# untitled.net
KiCad netlist of a schematic drawn in EAGLE
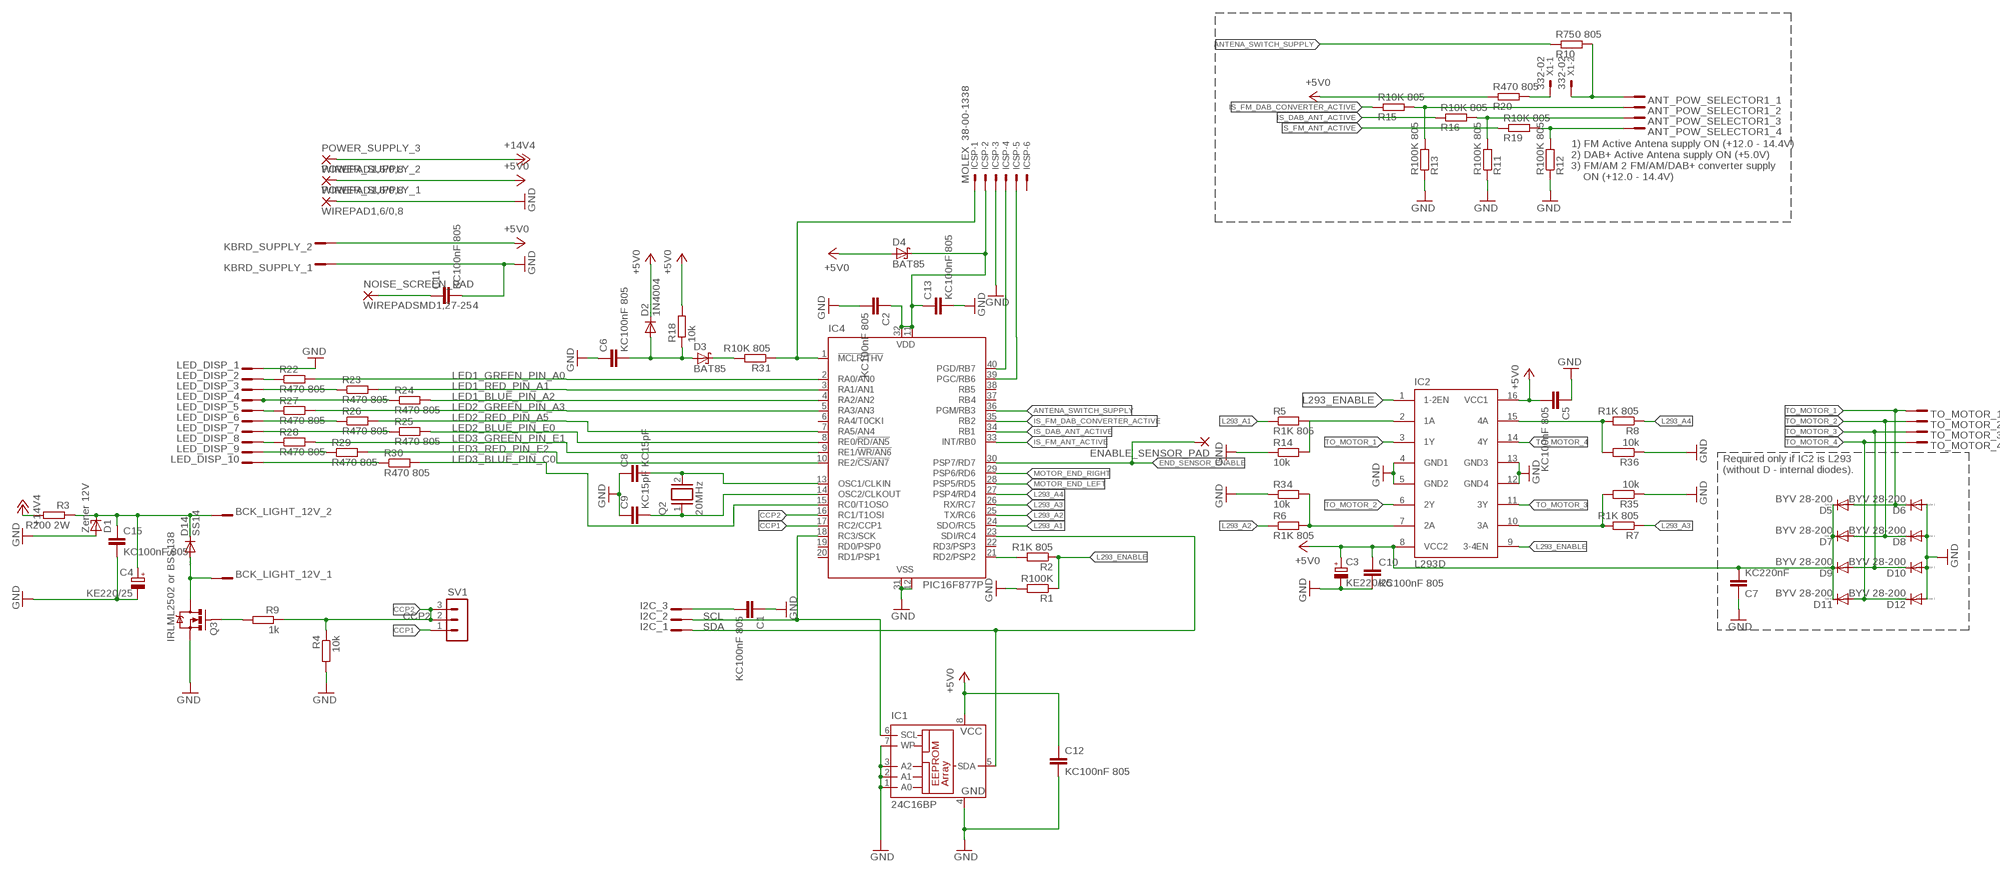
[diagram p0: schematic, sheet 1, part 1 of 2]
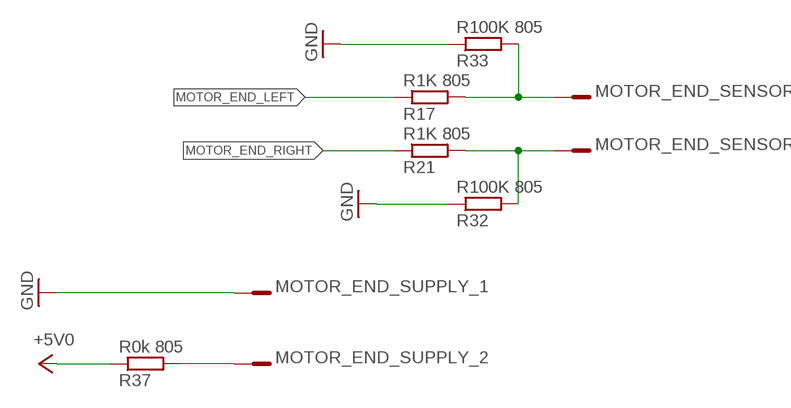
[diagram p1: schematic, sheet 1, part 2 of 2]

(export (version "E")
  (design (tool "Eeschema 10.0.6"))
  (components
    (comp (ref "ANT_POW_SELECTOR1")
      (value "JST_4_PIN_B4B-PH-KS")
      (footprint "eagle-import:B4B-PH-KS")
      (libsource (lib "eagle-import") (part "JST_4_PIN_B4B-PH-KS"))
    )
    (comp (ref "BCK_LIGHT_12V")
      (value "JST_2_PIN_B2B-XH-A")
      (footprint "eagle-import:B2B-XH-A")
      (libsource (lib "eagle-import") (part "JST_2_PIN_B2B-XH-A"))
    )
    (comp (ref "C1")
      (value "KC100nF 805")
      (footprint "eagle-import:C0805")
      (libsource (lib "eagle-import") (part "C-EUC0805"))
    )
    (comp (ref "C2")
      (value "KC100nF 805")
      (footprint "eagle-import:C0805")
      (libsource (lib "eagle-import") (part "C-EUC0805"))
    )
    (comp (ref "C3")
      (value "KE220/25")
      (footprint "eagle-import:E3,5-8")
      (libsource (lib "eagle-import") (part "CPOL-EUE3.5-8"))
    )
    (comp (ref "C4")
      (value "KE220/25")
      (footprint "eagle-import:TT2D7")
      (libsource (lib "eagle-import") (part "CPOL-EUTT2D7"))
    )
    (comp (ref "C5")
      (value "KC100nF 805")
      (footprint "eagle-import:C0805")
      (libsource (lib "eagle-import") (part "C-EUC0805"))
    )
    (comp (ref "C6")
      (value "KC100nF 805")
      (footprint "eagle-import:C0805")
      (libsource (lib "eagle-import") (part "C-EUC0805"))
    )
    (comp (ref "C7")
      (value "KC220nF")
      (footprint "eagle-import:C050-030X075")
      (libsource (lib "eagle-import") (part "C-EU050-030X075"))
    )
    (comp (ref "C8")
      (value "KC15pF")
      (footprint "eagle-import:C025-030X050")
      (libsource (lib "eagle-import") (part "C-EU025-030X050"))
    )
    (comp (ref "C9")
      (value "KC15pF")
      (footprint "eagle-import:C025-030X050")
      (libsource (lib "eagle-import") (part "C-EU025-030X050"))
    )
    (comp (ref "C10")
      (value "KC100nF 805")
      (footprint "eagle-import:C0805")
      (libsource (lib "eagle-import") (part "C-EUC0805"))
    )
    (comp (ref "C11")
      (value "KC100nF 805")
      (footprint "eagle-import:C0805")
      (libsource (lib "eagle-import") (part "C-EUC0805"))
    )
    (comp (ref "C12")
      (value "KC100nF 805")
      (footprint "eagle-import:C0805")
      (libsource (lib "eagle-import") (part "C-EUC0805"))
    )
    (comp (ref "C13")
      (value "KC100nF 805")
      (footprint "eagle-import:C0805")
      (libsource (lib "eagle-import") (part "C-EUC0805"))
    )
    (comp (ref "C15")
      (value "KC100nF 805")
      (footprint "eagle-import:C0805")
      (libsource (lib "eagle-import") (part "C-EUC0805"))
    )
    (comp (ref "D1")
      (value "Zener 12V")
      (footprint "eagle-import:ZDIO-5")
      (libsource (lib "eagle-import") (part "ZENER-DIODEZD-5"))
    )
    (comp (ref "D2")
      (value "1N4004")
      (footprint "eagle-import:DO41-7.6")
      (libsource (lib "eagle-import") (part "1N4004DO41-7.6"))
    )
    (comp (ref "D3")
      (value "BAT85")
      (footprint "eagle-import:DO34-5")
      (libsource (lib "eagle-import") (part "BAT85DO34-5"))
    )
    (comp (ref "D4")
      (value "BAT85")
      (footprint "eagle-import:DO34-5")
      (libsource (lib "eagle-import") (part "BAT85DO34-5"))
    )
    (comp (ref "D5")
      (value "BYV 28-200")
      (footprint "eagle-import:SOD64-10")
      (libsource (lib "eagle-import") (part "BYV28"))
    )
    (comp (ref "D6")
      (value "BYV 28-200")
      (footprint "eagle-import:SOD64-10")
      (libsource (lib "eagle-import") (part "BYV28"))
    )
    (comp (ref "D7")
      (value "BYV 28-200")
      (footprint "eagle-import:SOD64-10")
      (libsource (lib "eagle-import") (part "BYV28"))
    )
    (comp (ref "D8")
      (value "BYV 28-200")
      (footprint "eagle-import:SOD64-10")
      (libsource (lib "eagle-import") (part "BYV28"))
    )
    (comp (ref "D9")
      (value "BYV 28-200")
      (footprint "eagle-import:SOD64-10")
      (libsource (lib "eagle-import") (part "BYV28"))
    )
    (comp (ref "D10")
      (value "BYV 28-200")
      (footprint "eagle-import:SOD64-10")
      (libsource (lib "eagle-import") (part "BYV28"))
    )
    (comp (ref "D11")
      (value "BYV 28-200")
      (footprint "eagle-import:SOD64-10")
      (libsource (lib "eagle-import") (part "BYV28"))
    )
    (comp (ref "D12")
      (value "BYV 28-200")
      (footprint "eagle-import:SOD64-10")
      (libsource (lib "eagle-import") (part "BYV28"))
    )
    (comp (ref "D14")
      (value "SS14")
      (footprint "eagle-import:SMB")
      (libsource (lib "eagle-import") (part "DIODE-SMB"))
    )
    (comp (ref "ENABLE_SENSOR_PAD")
      (value "SMD2")
      (footprint "eagle-import:SMD1,27-2,54")
      (libsource (lib "eagle-import") (part "SMD2"))
    )
    (comp (ref "I2C")
      (value "JST_3_PIN_B3B-PH-KS")
      (footprint "eagle-import:B3B-PH-KS")
      (libsource (lib "eagle-import") (part "JST_3_PIN_B3B-PH-KS"))
    )
    (comp (ref "IC1")
      (value "24C16BP")
      (footprint "eagle-import:DIL8")
      (fields (field (name "MPN") "AT24C16B-PU"))
      (libsource (lib "eagle-import") (part "24PC16B"))
    )
    (comp (ref "IC2")
      (value "L293D")
      (footprint "eagle-import:DIL16")
      (libsource (lib "eagle-import") (part "L293D"))
    )
    (comp (ref "IC4")
      (value "PIC16F877P")
      (footprint "eagle-import:DIL40")
      (fields (field (name "MF") "MICROCHIP") (field (name "MPN") "PIC16F877-04/P"))
      (libsource (lib "eagle-import") (part "PIC16F87P7"))
    )
    (comp (ref "ICSP")
      (value "MOLEX 38-00-1338")
      (footprint "eagle-import:6410-06")
      (libsource (lib "eagle-import") (part "22-?-0627-2061"))
    )
    (comp (ref "KBRD_SUPPLY")
      (value "JST_2_PIN_B2B-PH-KS")
      (footprint "eagle-import:B2B-PH-KS")
      (libsource (lib "eagle-import") (part "JST_2_PIN_B2B-PH-KS"))
    )
    (comp (ref "LED_DISP")
      (value "JST_10_PIN_B10B-PH-KS")
      (footprint "eagle-import:B10B-PH-KS")
      (libsource (lib "eagle-import") (part "JST_10_PIN_B10B-PH-KS"))
    )
    (comp (ref "MOTOR_END_SENSOR")
      (value "JST_2_PIN_B2B-PH-KS")
      (footprint "eagle-import:B2B-PH-KS")
      (libsource (lib "eagle-import") (part "JST_2_PIN_B2B-PH-KS"))
    )
    (comp (ref "MOTOR_END_SUPPLY")
      (value "JST_2_PIN_B2B-PH-KS")
      (footprint "eagle-import:B2B-PH-KS")
      (libsource (lib "eagle-import") (part "JST_2_PIN_B2B-PH-KS"))
    )
    (comp (ref "NOISE_SCREEN_PAD")
      (value "WIREPADSMD1,27-254")
      (footprint "eagle-import:SMD1,27-2,54")
      (libsource (lib "eagle-import") (part "WIREPADSMD1,27-254"))
    )
    (comp (ref "POWER_SUPPLY_1")
      (value "WIREPAD1,6/0,8")
      (footprint "eagle-import:1,6_0,8")
      (libsource (lib "eagle-import") (part "WIREPAD1,6/0,8"))
    )
    (comp (ref "POWER_SUPPLY_2")
      (value "WIREPAD1,6/0,8")
      (footprint "eagle-import:1,6_0,8")
      (libsource (lib "eagle-import") (part "WIREPAD1,6/0,8"))
    )
    (comp (ref "POWER_SUPPLY_3")
      (value "WIREPAD1,6/0,8")
      (footprint "eagle-import:1,6_0,8")
      (libsource (lib "eagle-import") (part "WIREPAD1,6/0,8"))
    )
    (comp (ref "Q2")
      (value "20MHz")
      (footprint "eagle-import:QS")
      (libsource (lib "eagle-import") (part "XTAL/S"))
    )
    (comp (ref "Q3")
      (value "IRLML2502 or BSS138")
      (footprint "eagle-import:SOT23-3")
      (libsource (lib "eagle-import") (part "MOSFET-NCHANNELSMD"))
    )
    (comp (ref "R1")
      (value "R100K")
      (footprint "eagle-import:0204_7")
      (libsource (lib "eagle-import") (part "resistor_R-EU_0204/7"))
    )
    (comp (ref "R2")
      (value "R1K 805")
      (footprint "eagle-import:R0805")
      (libsource (lib "eagle-import") (part "resistor_R-EU_R0805"))
    )
    (comp (ref "R3")
      (value "R200 2W")
      (footprint "eagle-import:0207_12")
      (libsource (lib "eagle-import") (part "R-EU_0207/12"))
    )
    (comp (ref "R4")
      (value "10k")
      (footprint "eagle-import:M0805")
      (libsource (lib "eagle-import") (part "R-EU_M0805"))
    )
    (comp (ref "R5")
      (value "R1K 805")
      (footprint "eagle-import:R0805")
      (libsource (lib "eagle-import") (part "resistor_R-EU_R0805"))
    )
    (comp (ref "R6")
      (value "R1K 805")
      (footprint "eagle-import:R0805")
      (libsource (lib "eagle-import") (part "resistor_R-EU_R0805"))
    )
    (comp (ref "R7")
      (value "R1K 805")
      (footprint "eagle-import:R0805")
      (libsource (lib "eagle-import") (part "resistor_R-EU_R0805"))
    )
    (comp (ref "R8")
      (value "R1K 805")
      (footprint "eagle-import:R0805")
      (libsource (lib "eagle-import") (part "resistor_R-EU_R0805"))
    )
    (comp (ref "R9")
      (value "1k")
      (footprint "eagle-import:0207_12")
      (libsource (lib "eagle-import") (part "R-EU_0207/12"))
    )
    (comp (ref "R10")
      (value "R750 805")
      (footprint "eagle-import:R0805")
      (libsource (lib "eagle-import") (part "resistor_R-EU_R0805"))
    )
    (comp (ref "R11")
      (value "R100K 805")
      (footprint "eagle-import:R0805")
      (libsource (lib "eagle-import") (part "resistor_R-EU_R0805"))
    )
    (comp (ref "R12")
      (value "R100K 805")
      (footprint "eagle-import:R0805")
      (libsource (lib "eagle-import") (part "resistor_R-EU_R0805"))
    )
    (comp (ref "R13")
      (value "R100K 805")
      (footprint "eagle-import:R0805")
      (libsource (lib "eagle-import") (part "resistor_R-EU_R0805"))
    )
    (comp (ref "R14")
      (value "10k")
      (footprint "eagle-import:0204V")
      (libsource (lib "eagle-import") (part "resistor_R-EU_0204/2V"))
    )
    (comp (ref "R15")
      (value "R10K 805")
      (footprint "eagle-import:R0805")
      (libsource (lib "eagle-import") (part "resistor_R-EU_R0805"))
    )
    (comp (ref "R16")
      (value "R10K 805")
      (footprint "eagle-import:R0805")
      (libsource (lib "eagle-import") (part "resistor_R-EU_R0805"))
    )
    (comp (ref "R17")
      (value "R1K 805")
      (footprint "eagle-import:R0805")
      (libsource (lib "eagle-import") (part "resistor_R-EU_R0805"))
    )
    (comp (ref "R18")
      (value "10k")
      (footprint "eagle-import:R0805")
      (libsource (lib "eagle-import") (part "resistor_R-EU_R0805"))
    )
    (comp (ref "R19")
      (value "R10K 805")
      (footprint "eagle-import:R0805")
      (libsource (lib "eagle-import") (part "resistor_R-EU_R0805"))
    )
    (comp (ref "R20")
      (value "R470 805")
      (footprint "eagle-import:R0805")
      (libsource (lib "eagle-import") (part "resistor_R-EU_R0805"))
    )
    (comp (ref "R21")
      (value "R1K 805")
      (footprint "eagle-import:R0805")
      (libsource (lib "eagle-import") (part "resistor_R-EU_R0805"))
    )
    (comp (ref "R22")
      (value "R470 805")
      (footprint "eagle-import:R0805")
      (libsource (lib "eagle-import") (part "resistor_R-EU_R0805"))
    )
    (comp (ref "R23")
      (value "R470 805")
      (footprint "eagle-import:R0805")
      (libsource (lib "eagle-import") (part "resistor_R-EU_R0805"))
    )
    (comp (ref "R24")
      (value "R470 805")
      (footprint "eagle-import:R0805")
      (libsource (lib "eagle-import") (part "resistor_R-EU_R0805"))
    )
    (comp (ref "R25")
      (value "R470 805")
      (footprint "eagle-import:R0805")
      (libsource (lib "eagle-import") (part "resistor_R-EU_R0805"))
    )
    (comp (ref "R26")
      (value "R470 805")
      (footprint "eagle-import:R0805")
      (libsource (lib "eagle-import") (part "resistor_R-EU_R0805"))
    )
    (comp (ref "R27")
      (value "R470 805")
      (footprint "eagle-import:R0805")
      (libsource (lib "eagle-import") (part "resistor_R-EU_R0805"))
    )
    (comp (ref "R28")
      (value "R470 805")
      (footprint "eagle-import:R0805")
      (libsource (lib "eagle-import") (part "resistor_R-EU_R0805"))
    )
    (comp (ref "R29")
      (value "R470 805")
      (footprint "eagle-import:R0805")
      (libsource (lib "eagle-import") (part "resistor_R-EU_R0805"))
    )
    (comp (ref "R30")
      (value "R470 805")
      (footprint "eagle-import:R0805")
      (libsource (lib "eagle-import") (part "resistor_R-EU_R0805"))
    )
    (comp (ref "R31")
      (value "R10K 805")
      (footprint "eagle-import:R0805")
      (libsource (lib "eagle-import") (part "resistor_R-EU_R0805"))
    )
    (comp (ref "R32")
      (value "R100K 805")
      (footprint "eagle-import:R0805")
      (libsource (lib "eagle-import") (part "resistor_R-EU_R0805"))
    )
    (comp (ref "R33")
      (value "R100K 805")
      (footprint "eagle-import:R0805")
      (libsource (lib "eagle-import") (part "resistor_R-EU_R0805"))
    )
    (comp (ref "R34")
      (value "10k")
      (footprint "eagle-import:0204_5")
      (libsource (lib "eagle-import") (part "resistor_R-EU_0204/5"))
    )
    (comp (ref "R35")
      (value "10k")
      (footprint "eagle-import:0204_7")
      (libsource (lib "eagle-import") (part "resistor_R-EU_0204/7"))
    )
    (comp (ref "R36")
      (value "10k")
      (footprint "eagle-import:0204_7")
      (libsource (lib "eagle-import") (part "resistor_R-EU_0204/7"))
    )
    (comp (ref "R37")
      (value "R0k 805")
      (footprint "eagle-import:R0805")
      (libsource (lib "eagle-import") (part "resistor_R-EU_R0805"))
    )
    (comp (ref "SV1")
      (value "MA03-1")
      (footprint "eagle-import:MA03-1")
      (libsource (lib "eagle-import") (part "MA03-1"))
    )
    (comp (ref "TO_MOTOR")
      (value "JST_4_PIN_B4B-XH-A")
      (footprint "eagle-import:B4B-XH-A")
      (libsource (lib "eagle-import") (part "JST_4_PIN_B4B-XH-A"))
    )
    (comp (ref "X1")
      (value "332-02")
      (footprint "eagle-import:332-02")
      (libsource (lib "eagle-import") (part "332-02"))
    )
  )
  (nets
    (net (code "1") (name "+5V0") (class "Default")
      (node (ref "C10") (pin "1") (pinfunction "1_1") (pintype "passive"))
      (node (ref "C12") (pin "1") (pinfunction "1_1") (pintype "passive"))
      (node (ref "C3") (pin "+") (pinfunction "+_+") (pintype "passive"))
      (node (ref "C5") (pin "2") (pinfunction "2_2") (pintype "passive"))
      (node (ref "C7") (pin "2") (pinfunction "2_2") (pintype "passive"))
      (node (ref "D11") (pin "C") (pinfunction "C_C") (pintype "passive"))
      (node (ref "D2") (pin "C") (pinfunction "C_C") (pintype "passive"))
      (node (ref "D4") (pin "A") (pinfunction "A_A") (pintype "passive"))
      (node (ref "D5") (pin "C") (pinfunction "C_C") (pintype "passive"))
      (node (ref "D7") (pin "C") (pinfunction "C_C") (pintype "passive"))
      (node (ref "D9") (pin "C") (pinfunction "C_C") (pintype "passive"))
      (node (ref "IC1") (pin "8") (pinfunction "VCC_8") (pintype "power_in"))
      (node (ref "IC2") (pin "16") (pinfunction "VCC1_16") (pintype "power_in"))
      (node (ref "IC2") (pin "8") (pinfunction "VCC2_8") (pintype "power_in"))
      (node (ref "KBRD_SUPPLY") (pin "P$2") (pinfunction "P$1_P$2") (pintype "bidirectional"))
      (node (ref "POWER_SUPPLY_2") (pin "1") (pinfunction "P_1") (pintype "passive"))
      (node (ref "R18") (pin "2") (pinfunction "2_2") (pintype "passive"))
      (node (ref "R20") (pin "1") (pinfunction "1_1") (pintype "passive"))
      (node (ref "R37") (pin "1") (pinfunction "1_1") (pintype "passive"))
    )
    (net (code "2") (name "+14V4") (class "Default")
      (node (ref "POWER_SUPPLY_3") (pin "1") (pinfunction "P_1") (pintype "passive"))
      (node (ref "R3") (pin "2") (pinfunction "2_2") (pintype "passive"))
    )
    (net (code "3") (name "/LED1_BLUE_PIN_A2") (class "Default")
      (node (ref "IC4") (pin "4") (pinfunction "RA2/AN2_4") (pintype "bidirectional"))
      (node (ref "R24") (pin "2") (pinfunction "2_2") (pintype "passive"))
    )
    (net (code "4") (name "/LED1_GREEN_PIN_A0") (class "Default")
      (node (ref "IC4") (pin "2") (pinfunction "RA0/AN0_2") (pintype "bidirectional"))
      (node (ref "R22") (pin "2") (pinfunction "2_2") (pintype "passive"))
    )
    (net (code "5") (name "/LED1_RED_PIN_A1") (class "Default")
      (node (ref "IC4") (pin "3") (pinfunction "RA1/AN1_3") (pintype "bidirectional"))
      (node (ref "R23") (pin "2") (pinfunction "2_2") (pintype "passive"))
    )
    (net (code "6") (name "/LED2_BLUE_PIN_E0") (class "Default")
      (node (ref "IC4") (pin "8") (pinfunction "RE0/~{RD/AN5}_8") (pintype "bidirectional"))
      (node (ref "R25") (pin "2") (pinfunction "2_2") (pintype "passive"))
    )
    (net (code "7") (name "/LED2_GREEN_PIN_A3") (class "Default")
      (node (ref "IC4") (pin "5") (pinfunction "RA3/AN3_5") (pintype "bidirectional"))
      (node (ref "R27") (pin "2") (pinfunction "2_2") (pintype "passive"))
    )
    (net (code "8") (name "/LED2_RED_PIN_A5") (class "Default")
      (node (ref "IC4") (pin "7") (pinfunction "RA5/AN4_7") (pintype "bidirectional"))
      (node (ref "R26") (pin "2") (pinfunction "2_2") (pintype "passive"))
    )
    (net (code "9") (name "/LED3_BLUE_PIN_C0") (class "Default")
      (node (ref "IC4") (pin "15") (pinfunction "RC0/T1OSO_15") (pintype "bidirectional"))
      (node (ref "R30") (pin "2") (pinfunction "2_2") (pintype "passive"))
    )
    (net (code "10") (name "/LED3_GREEN_PIN_E1") (class "Default")
      (node (ref "IC4") (pin "9") (pinfunction "RE1/~{WR/AN6}_9") (pintype "bidirectional"))
      (node (ref "R28") (pin "2") (pinfunction "2_2") (pintype "passive"))
    )
    (net (code "11") (name "/LED3_RED_PIN_E2") (class "Default")
      (node (ref "IC4") (pin "10") (pinfunction "RE2/~{CS/AN7}_10") (pintype "bidirectional"))
      (node (ref "R29") (pin "2") (pinfunction "2_2") (pintype "passive"))
    )
    (net (code "12") (name "/SCL") (class "Default")
      (node (ref "I2C") (pin "P$2") (pinfunction "P$1_P$2") (pintype "bidirectional"))
      (node (ref "IC1") (pin "6") (pinfunction "SCL_6") (pintype "input"))
      (node (ref "IC4") (pin "18") (pinfunction "RC3/SCK_18") (pintype "bidirectional"))
    )
    (net (code "13") (name "/SDA") (class "Default")
      (node (ref "I2C") (pin "P$1") (pinfunction "P$1_P$1") (pintype "bidirectional"))
      (node (ref "IC1") (pin "5") (pinfunction "SDA_5") (pintype "bidirectional"))
      (node (ref "IC4") (pin "23") (pinfunction "SDI/RC4_23") (pintype "bidirectional"))
    )
    (net (code "14") (name "ANTENA_SWITCH_SUPPLY") (class "Default")
      (node (ref "IC4") (pin "36") (pinfunction "PGM/RB3_36") (pintype "bidirectional"))
      (node (ref "R10") (pin "1") (pinfunction "1_1") (pintype "passive"))
    )
    (net (code "15") (name "CCP1") (class "Default")
      (node (ref "IC4") (pin "17") (pinfunction "RC2/CCP1_17") (pintype "bidirectional"))
      (node (ref "SV1") (pin "1") (pinfunction "1_1") (pintype "passive"))
    )
    (net (code "16") (name "CCP2") (class "Default")
      (node (ref "IC4") (pin "16") (pinfunction "RC1/T1OSI_16") (pintype "bidirectional"))
      (node (ref "R4") (pin "1") (pinfunction "1_1") (pintype "passive"))
      (node (ref "R9") (pin "1") (pinfunction "1_1") (pintype "passive"))
      (node (ref "SV1") (pin "2") (pinfunction "2_2") (pintype "passive"))
      (node (ref "SV1") (pin "3") (pinfunction "3_3") (pintype "passive"))
    )
    (net (code "17") (name "END_SENSOR_ENABLE") (class "Default")
      (node (ref "ENABLE_SENSOR_PAD") (pin "1") (pinfunction "P_1") (pintype "passive"))
      (node (ref "IC4") (pin "30") (pinfunction "PSP7/RD7_30") (pintype "bidirectional"))
    )
    (net (code "18") (name "GND") (class "Default")
      (node (ref "C1") (pin "1") (pinfunction "1_1") (pintype "passive"))
      (node (ref "C10") (pin "2") (pinfunction "2_2") (pintype "passive"))
      (node (ref "C11") (pin "2") (pinfunction "2_2") (pintype "passive"))
      (node (ref "C12") (pin "2") (pinfunction "2_2") (pintype "passive"))
      (node (ref "C13") (pin "2") (pinfunction "2_2") (pintype "passive"))
      (node (ref "C15") (pin "2") (pinfunction "2_2") (pintype "passive"))
      (node (ref "C2") (pin "2") (pinfunction "2_2") (pintype "passive"))
      (node (ref "C3") (pin "-") (pinfunction "-_-") (pintype "passive"))
      (node (ref "C4") (pin "-") (pinfunction "-_-") (pintype "passive"))
      (node (ref "C5") (pin "1") (pinfunction "1_1") (pintype "passive"))
      (node (ref "C6") (pin "1") (pinfunction "1_1") (pintype "passive"))
      (node (ref "C7") (pin "1") (pinfunction "1_1") (pintype "passive"))
      (node (ref "C8") (pin "1") (pinfunction "1_1") (pintype "passive"))
      (node (ref "C9") (pin "1") (pinfunction "1_1") (pintype "passive"))
      (node (ref "D1") (pin "A") (pinfunction "A_A") (pintype "passive"))
      (node (ref "D10") (pin "A") (pinfunction "A_A") (pintype "passive"))
      (node (ref "D12") (pin "A") (pinfunction "A_A") (pintype "passive"))
      (node (ref "D6") (pin "A") (pinfunction "A_A") (pintype "passive"))
      (node (ref "D8") (pin "A") (pinfunction "A_A") (pintype "passive"))
      (node (ref "IC1") (pin "1") (pinfunction "A0_1") (pintype "input"))
      (node (ref "IC1") (pin "2") (pinfunction "A1_2") (pintype "input"))
      (node (ref "IC1") (pin "3") (pinfunction "A2_3") (pintype "input"))
      (node (ref "IC1") (pin "4") (pinfunction "GND_4") (pintype "power_in"))
      (node (ref "IC1") (pin "7") (pinfunction "WP_7") (pintype "input"))
      (node (ref "IC2") (pin "12") (pinfunction "GND4_12") (pintype "power_in"))
      (node (ref "IC2") (pin "13") (pinfunction "GND3_13") (pintype "power_in"))
      (node (ref "IC2") (pin "4") (pinfunction "GND1_4") (pintype "power_in"))
      (node (ref "IC2") (pin "5") (pinfunction "GND2_5") (pintype "power_in"))
      (node (ref "IC4") (pin "12") (pinfunction "VSS_12") (pintype "power_in"))
      (node (ref "IC4") (pin "31") (pinfunction "VSS_31") (pintype "power_in"))
      (node (ref "ICSP") (pin "3") (pinfunction "S_3") (pintype "passive"))
      (node (ref "KBRD_SUPPLY") (pin "P$1") (pinfunction "P$1_P$1") (pintype "bidirectional"))
      (node (ref "LED_DISP") (pin "P$1") (pinfunction "P$1_P$1") (pintype "bidirectional"))
      (node (ref "MOTOR_END_SUPPLY") (pin "P$1") (pinfunction "P$1_P$1") (pintype "bidirectional"))
      (node (ref "POWER_SUPPLY_1") (pin "1") (pinfunction "P_1") (pintype "passive"))
      (node (ref "Q3") (pin "2") (pinfunction "S_2") (pintype "passive"))
      (node (ref "R1") (pin "2") (pinfunction "2_2") (pintype "passive"))
      (node (ref "R11") (pin "1") (pinfunction "1_1") (pintype "passive"))
      (node (ref "R12") (pin "1") (pinfunction "1_1") (pintype "passive"))
      (node (ref "R13") (pin "1") (pinfunction "1_1") (pintype "passive"))
      (node (ref "R14") (pin "1") (pinfunction "1_1") (pintype "passive"))
      (node (ref "R32") (pin "1") (pinfunction "1_1") (pintype "passive"))
      (node (ref "R33") (pin "1") (pinfunction "1_1") (pintype "passive"))
      (node (ref "R34") (pin "1") (pinfunction "1_1") (pintype "passive"))
      (node (ref "R35") (pin "1") (pinfunction "1_1") (pintype "passive"))
      (node (ref "R36") (pin "1") (pinfunction "1_1") (pintype "passive"))
      (node (ref "R4") (pin "2") (pinfunction "2_2") (pintype "passive"))
    )
    (net (code "19") (name "IS_DAB_ANT_ACTIVE") (class "Default")
      (node (ref "IC4") (pin "34") (pinfunction "RB1_34") (pintype "bidirectional"))
      (node (ref "R16") (pin "1") (pinfunction "1_1") (pintype "passive"))
    )
    (net (code "20") (name "IS_FM_ANT_ACTIVE") (class "Default")
      (node (ref "IC4") (pin "33") (pinfunction "INT/RB0_33") (pintype "bidirectional"))
      (node (ref "R19") (pin "1") (pinfunction "1_1") (pintype "passive"))
    )
    (net (code "21") (name "IS_FM_DAB_CONVERTER_ACTIVE") (class "Default")
      (node (ref "IC4") (pin "35") (pinfunction "RB2_35") (pintype "bidirectional"))
      (node (ref "R15") (pin "1") (pinfunction "1_1") (pintype "passive"))
    )
    (net (code "22") (name "L293_A1") (class "Default")
      (node (ref "IC4") (pin "24") (pinfunction "SDO/RC5_24") (pintype "bidirectional"))
      (node (ref "R5") (pin "1") (pinfunction "1_1") (pintype "passive"))
    )
    (net (code "23") (name "L293_A2") (class "Default")
      (node (ref "IC4") (pin "25") (pinfunction "TX/RC6_25") (pintype "bidirectional"))
      (node (ref "R6") (pin "1") (pinfunction "1_1") (pintype "passive"))
    )
    (net (code "24") (name "L293_A3") (class "Default")
      (node (ref "IC4") (pin "26") (pinfunction "RX/RC7_26") (pintype "bidirectional"))
      (node (ref "R7") (pin "1") (pinfunction "1_1") (pintype "passive"))
    )
    (net (code "25") (name "L293_A4") (class "Default")
      (node (ref "IC4") (pin "27") (pinfunction "PSP4/RD4_27") (pintype "bidirectional"))
      (node (ref "R8") (pin "1") (pinfunction "1_1") (pintype "passive"))
    )
    (net (code "26") (name "L293_ENABLE") (class "Default")
      (node (ref "IC2") (pin "1") (pinfunction "1-2EN_1") (pintype "input"))
      (node (ref "IC2") (pin "9") (pinfunction "3-4EN_9") (pintype "input"))
      (node (ref "R1") (pin "1") (pinfunction "1_1") (pintype "passive"))
      (node (ref "R2") (pin "1") (pinfunction "1_1") (pintype "passive"))
    )
    (net (code "27") (name "MOTOR_END_LEFT") (class "Default")
      (node (ref "IC4") (pin "28") (pinfunction "PSP5/RD5_28") (pintype "bidirectional"))
      (node (ref "R17") (pin "1") (pinfunction "1_1") (pintype "passive"))
    )
    (net (code "28") (name "MOTOR_END_RIGHT") (class "Default")
      (node (ref "IC4") (pin "29") (pinfunction "PSP6/RD6_29") (pintype "bidirectional"))
      (node (ref "R21") (pin "1") (pinfunction "1_1") (pintype "passive"))
    )
    (net (code "29") (name "Net-(ANT_POW_SELECTOR1B-P$1)") (class "Default")
      (node (ref "ANT_POW_SELECTOR1") (pin "P$2") (pinfunction "P$1_P$2") (pintype "bidirectional"))
      (node (ref "R13") (pin "2") (pinfunction "2_2") (pintype "passive"))
      (node (ref "R15") (pin "2") (pinfunction "2_2") (pintype "passive"))
    )
    (net (code "30") (name "Net-(ANT_POW_SELECTOR1C-P$1)") (class "Default")
      (node (ref "ANT_POW_SELECTOR1") (pin "P$3") (pinfunction "P$1_P$3") (pintype "bidirectional"))
      (node (ref "R11") (pin "2") (pinfunction "2_2") (pintype "passive"))
      (node (ref "R16") (pin "2") (pinfunction "2_2") (pintype "passive"))
    )
    (net (code "31") (name "Net-(ANT_POW_SELECTOR1D-P$1)") (class "Default")
      (node (ref "ANT_POW_SELECTOR1") (pin "P$4") (pinfunction "P$1_P$4") (pintype "bidirectional"))
      (node (ref "R12") (pin "2") (pinfunction "2_2") (pintype "passive"))
      (node (ref "R19") (pin "2") (pinfunction "2_2") (pintype "passive"))
    )
    (net (code "32") (name "Net-(BCK_LIGHT_12VB-P$1)") (class "Default")
      (node (ref "BCK_LIGHT_12V") (pin "P$2") (pinfunction "P$1_P$2") (pintype "bidirectional"))
      (node (ref "C15") (pin "1") (pinfunction "1_1") (pintype "passive"))
      (node (ref "C4") (pin "+") (pinfunction "+_+") (pintype "passive"))
      (node (ref "D1") (pin "C") (pinfunction "C_C") (pintype "passive"))
      (node (ref "D14") (pin "C") (pinfunction "C_C") (pintype "passive"))
      (node (ref "R3") (pin "1") (pinfunction "1_1") (pintype "passive"))
    )
    (net (code "33") (name "Net-(C6-Pad2)") (class "Default")
      (node (ref "C6") (pin "2") (pinfunction "2_2") (pintype "passive"))
      (node (ref "D2") (pin "A") (pinfunction "A_A") (pintype "passive"))
      (node (ref "D3") (pin "A") (pinfunction "A_A") (pintype "passive"))
      (node (ref "R18") (pin "1") (pinfunction "1_1") (pintype "passive"))
    )
    (net (code "34") (name "Net-(D3-PadC)") (class "Default")
      (node (ref "D3") (pin "C") (pinfunction "C_C") (pintype "passive"))
      (node (ref "R31") (pin "2") (pinfunction "2_2") (pintype "passive"))
    )
    (net (code "35") (name "Net-(I2CC-P$1)") (class "Default")
      (node (ref "C1") (pin "2") (pinfunction "2_2") (pintype "passive"))
      (node (ref "I2C") (pin "P$3") (pinfunction "P$1_P$3") (pintype "bidirectional"))
    )
    (net (code "36") (name "Net-(IC2-1A)") (class "Default")
      (node (ref "IC2") (pin "2") (pinfunction "1A_2") (pintype "input"))
      (node (ref "R14") (pin "2") (pinfunction "2_2") (pintype "passive"))
      (node (ref "R5") (pin "2") (pinfunction "2_2") (pintype "passive"))
    )
    (net (code "37") (name "Net-(IC2-2A)") (class "Default")
      (node (ref "IC2") (pin "7") (pinfunction "2A_7") (pintype "input"))
      (node (ref "R34") (pin "2") (pinfunction "2_2") (pintype "passive"))
      (node (ref "R6") (pin "2") (pinfunction "2_2") (pintype "passive"))
    )
    (net (code "38") (name "Net-(IC2-3A)") (class "Default")
      (node (ref "IC2") (pin "10") (pinfunction "3A_10") (pintype "input"))
      (node (ref "R35") (pin "2") (pinfunction "2_2") (pintype "passive"))
      (node (ref "R7") (pin "2") (pinfunction "2_2") (pintype "passive"))
    )
    (net (code "39") (name "Net-(IC2-4A)") (class "Default")
      (node (ref "IC2") (pin "15") (pinfunction "4A_15") (pintype "input"))
      (node (ref "R36") (pin "2") (pinfunction "2_2") (pintype "passive"))
      (node (ref "R8") (pin "2") (pinfunction "2_2") (pintype "passive"))
    )
    (net (code "40") (name "Net-(IC4-OSC1{slash}CLKIN)") (class "Default")
      (node (ref "C8") (pin "2") (pinfunction "2_2") (pintype "passive"))
      (node (ref "IC4") (pin "13") (pinfunction "OSC1/CLKIN_13") (pintype "input"))
      (node (ref "Q2") (pin "2") (pinfunction "2_2") (pintype "passive"))
    )
    (net (code "41") (name "Net-(IC4-OSC2{slash}CLKOUT)") (class "Default")
      (node (ref "C9") (pin "2") (pinfunction "2_2") (pintype "passive"))
      (node (ref "IC4") (pin "14") (pinfunction "OSC2/CLKOUT_14") (pintype "output"))
      (node (ref "Q2") (pin "1") (pinfunction "1_1") (pintype "passive"))
    )
    (net (code "42") (name "Net-(IC4-PGC{slash}RB6)") (class "Default")
      (node (ref "IC4") (pin "39") (pinfunction "PGC/RB6_39") (pintype "bidirectional"))
      (node (ref "ICSP") (pin "5") (pinfunction "S_5") (pintype "passive"))
    )
    (net (code "43") (name "Net-(IC4-PGD{slash}RB7)") (class "Default")
      (node (ref "IC4") (pin "40") (pinfunction "PGD/RB7_40") (pintype "bidirectional"))
      (node (ref "ICSP") (pin "4") (pinfunction "S_4") (pintype "passive"))
    )
    (net (code "44") (name "Net-(IC4-RD2{slash}PSP2)") (class "Default")
      (node (ref "IC4") (pin "21") (pinfunction "RD2/PSP2_21") (pintype "bidirectional"))
      (node (ref "R2") (pin "2") (pinfunction "2_2") (pintype "passive"))
    )
    (net (code "45") (name "Net-(IC4-~{MCLR{slash}THV})") (class "Default")
      (node (ref "IC4") (pin "1") (pinfunction "~{MCLR/THV}_1") (pintype "input"))
      (node (ref "ICSP") (pin "1") (pinfunction "S_1") (pintype "passive"))
      (node (ref "R31") (pin "1") (pinfunction "1_1") (pintype "passive"))
    )
    (net (code "46") (name "Net-(ICSPB-S)") (class "Default")
      (node (ref "C13") (pin "1") (pinfunction "1_1") (pintype "passive"))
      (node (ref "C2") (pin "1") (pinfunction "1_1") (pintype "passive"))
      (node (ref "D4") (pin "C") (pinfunction "C_C") (pintype "passive"))
      (node (ref "IC4") (pin "11") (pinfunction "VDD_11") (pintype "power_in"))
      (node (ref "IC4") (pin "32") (pinfunction "VDD_32") (pintype "power_in"))
      (node (ref "ICSP") (pin "2") (pinfunction "S_2") (pintype "passive"))
    )
    (net (code "47") (name "Net-(LED_DISPB-P$1)") (class "Default")
      (node (ref "LED_DISP") (pin "P$10") (pinfunction "P$1_P$10") (pintype "bidirectional"))
      (node (ref "R30") (pin "1") (pinfunction "1_1") (pintype "passive"))
    )
    (net (code "48") (name "Net-(LED_DISPC-P$1)") (class "Default")
      (node (ref "LED_DISP") (pin "P$2") (pinfunction "P$1_P$2") (pintype "bidirectional"))
      (node (ref "R22") (pin "1") (pinfunction "1_1") (pintype "passive"))
    )
    (net (code "49") (name "Net-(LED_DISPD-P$1)") (class "Default")
      (node (ref "LED_DISP") (pin "P$3") (pinfunction "P$1_P$3") (pintype "bidirectional"))
      (node (ref "R23") (pin "1") (pinfunction "1_1") (pintype "passive"))
    )
    (net (code "50") (name "Net-(LED_DISPE-P$1)") (class "Default")
      (node (ref "LED_DISP") (pin "P$4") (pinfunction "P$1_P$4") (pintype "bidirectional"))
      (node (ref "R24") (pin "1") (pinfunction "1_1") (pintype "passive"))
    )
    (net (code "51") (name "Net-(LED_DISPF-P$1)") (class "Default")
      (node (ref "LED_DISP") (pin "P$5") (pinfunction "P$1_P$5") (pintype "bidirectional"))
      (node (ref "R27") (pin "1") (pinfunction "1_1") (pintype "passive"))
    )
    (net (code "52") (name "Net-(LED_DISPG-P$1)") (class "Default")
      (node (ref "LED_DISP") (pin "P$6") (pinfunction "P$1_P$6") (pintype "bidirectional"))
      (node (ref "R26") (pin "1") (pinfunction "1_1") (pintype "passive"))
    )
    (net (code "53") (name "Net-(LED_DISPH-P$1)") (class "Default")
      (node (ref "LED_DISP") (pin "P$7") (pinfunction "P$1_P$7") (pintype "bidirectional"))
      (node (ref "R25") (pin "1") (pinfunction "1_1") (pintype "passive"))
    )
    (net (code "54") (name "Net-(LED_DISPI-P$1)") (class "Default")
      (node (ref "LED_DISP") (pin "P$8") (pinfunction "P$1_P$8") (pintype "bidirectional"))
      (node (ref "R28") (pin "1") (pinfunction "1_1") (pintype "passive"))
    )
    (net (code "55") (name "Net-(LED_DISPJ-P$1)") (class "Default")
      (node (ref "LED_DISP") (pin "P$9") (pinfunction "P$1_P$9") (pintype "bidirectional"))
      (node (ref "R29") (pin "1") (pinfunction "1_1") (pintype "passive"))
    )
    (net (code "56") (name "Net-(MOTOR_END_SENSOR-PadP$1)") (class "Default")
      (node (ref "MOTOR_END_SENSOR") (pin "P$1") (pinfunction "P$1_P$1") (pintype "bidirectional"))
      (node (ref "R21") (pin "2") (pinfunction "2_2") (pintype "passive"))
      (node (ref "R32") (pin "2") (pinfunction "2_2") (pintype "passive"))
    )
    (net (code "57") (name "Net-(MOTOR_END_SENSORB-P$1)") (class "Default")
      (node (ref "MOTOR_END_SENSOR") (pin "P$2") (pinfunction "P$1_P$2") (pintype "bidirectional"))
      (node (ref "R17") (pin "2") (pinfunction "2_2") (pintype "passive"))
      (node (ref "R33") (pin "2") (pinfunction "2_2") (pintype "passive"))
    )
    (net (code "58") (name "Net-(MOTOR_END_SUPPLYB-P$1)") (class "Default")
      (node (ref "MOTOR_END_SUPPLY") (pin "P$2") (pinfunction "P$1_P$2") (pintype "bidirectional"))
      (node (ref "R37") (pin "2") (pinfunction "2_2") (pintype "passive"))
    )
    (net (code "59") (name "Net-(NOISE_SCREEN_PAD-P)") (class "Default")
      (node (ref "C11") (pin "1") (pinfunction "1_1") (pintype "passive"))
      (node (ref "NOISE_SCREEN_PAD") (pin "1") (pinfunction "P_1") (pintype "passive"))
    )
    (net (code "60") (name "Net-(Q3-D)") (class "Default")
      (node (ref "BCK_LIGHT_12V") (pin "P$1") (pinfunction "P$1_P$1") (pintype "bidirectional"))
      (node (ref "D14") (pin "A") (pinfunction "A_A") (pintype "passive"))
      (node (ref "Q3") (pin "3") (pinfunction "D_3") (pintype "passive"))
    )
    (net (code "61") (name "Net-(Q3-G)") (class "Default")
      (node (ref "Q3") (pin "1") (pinfunction "G_1") (pintype "passive"))
      (node (ref "R9") (pin "2") (pinfunction "2_2") (pintype "passive"))
    )
    (net (code "62") (name "Net-(X1A-S)") (class "Default")
      (node (ref "R20") (pin "2") (pinfunction "2_2") (pintype "passive"))
      (node (ref "X1") (pin "1") (pinfunction "S_1") (pintype "passive"))
    )
    (net (code "63") (name "Net-(X1B-S)") (class "Default")
      (node (ref "ANT_POW_SELECTOR1") (pin "P$1") (pinfunction "P$1_P$1") (pintype "bidirectional"))
      (node (ref "R10") (pin "2") (pinfunction "2_2") (pintype "passive"))
      (node (ref "X1") (pin "2") (pinfunction "S_2") (pintype "passive"))
    )
    (net (code "64") (name "TO_MOTOR_1") (class "Default")
      (node (ref "D5") (pin "A") (pinfunction "A_A") (pintype "passive"))
      (node (ref "D6") (pin "C") (pinfunction "C_C") (pintype "passive"))
      (node (ref "IC2") (pin "3") (pinfunction "1Y_3") (pintype "output"))
      (node (ref "TO_MOTOR") (pin "P$1") (pinfunction "P$1_P$1") (pintype "bidirectional"))
    )
    (net (code "65") (name "TO_MOTOR_2") (class "Default")
      (node (ref "D7") (pin "A") (pinfunction "A_A") (pintype "passive"))
      (node (ref "D8") (pin "C") (pinfunction "C_C") (pintype "passive"))
      (node (ref "IC2") (pin "6") (pinfunction "2Y_6") (pintype "output"))
      (node (ref "TO_MOTOR") (pin "P$2") (pinfunction "P$1_P$2") (pintype "bidirectional"))
    )
    (net (code "66") (name "TO_MOTOR_3") (class "Default")
      (node (ref "D10") (pin "C") (pinfunction "C_C") (pintype "passive"))
      (node (ref "D9") (pin "A") (pinfunction "A_A") (pintype "passive"))
      (node (ref "IC2") (pin "11") (pinfunction "3Y_11") (pintype "output"))
      (node (ref "TO_MOTOR") (pin "P$3") (pinfunction "P$1_P$3") (pintype "bidirectional"))
    )
    (net (code "67") (name "TO_MOTOR_4") (class "Default")
      (node (ref "D11") (pin "A") (pinfunction "A_A") (pintype "passive"))
      (node (ref "D12") (pin "C") (pinfunction "C_C") (pintype "passive"))
      (node (ref "IC2") (pin "14") (pinfunction "4Y_14") (pintype "output"))
      (node (ref "TO_MOTOR") (pin "P$4") (pinfunction "P$1_P$4") (pintype "bidirectional"))
    )
    (net (code "68") (name "unconnected-(IC4-RA4{slash}T0CKI-Pad6)") (class "Default")
      (node (ref "IC4") (pin "6") (pinfunction "RA4/T0CKI_6") (pintype "bidirectional"))
    )
    (net (code "69") (name "unconnected-(IC4-RB4-Pad37)") (class "Default")
      (node (ref "IC4") (pin "37") (pinfunction "RB4_37") (pintype "bidirectional"))
    )
    (net (code "70") (name "unconnected-(IC4-RB5-Pad38)") (class "Default")
      (node (ref "IC4") (pin "38") (pinfunction "RB5_38") (pintype "bidirectional"))
    )
    (net (code "71") (name "unconnected-(IC4-RD0{slash}PSP0-Pad19)") (class "Default")
      (node (ref "IC4") (pin "19") (pinfunction "RD0/PSP0_19") (pintype "bidirectional"))
    )
    (net (code "72") (name "unconnected-(IC4-RD1{slash}PSP1-Pad20)") (class "Default")
      (node (ref "IC4") (pin "20") (pinfunction "RD1/PSP1_20") (pintype "bidirectional"))
    )
    (net (code "73") (name "unconnected-(IC4-RD3{slash}PSP3-Pad22)") (class "Default")
      (node (ref "IC4") (pin "22") (pinfunction "RD3/PSP3_22") (pintype "bidirectional"))
    )
    (net (code "74") (name "unconnected-(ICSPF-S-Pad6)") (class "Default")
      (node (ref "ICSP") (pin "6") (pinfunction "S_6") (pintype "passive"))
    )
  )
)
